# JetsonTK1_GPIO_V2.net
KiCad netlist of a schematic drawn in EAGLE
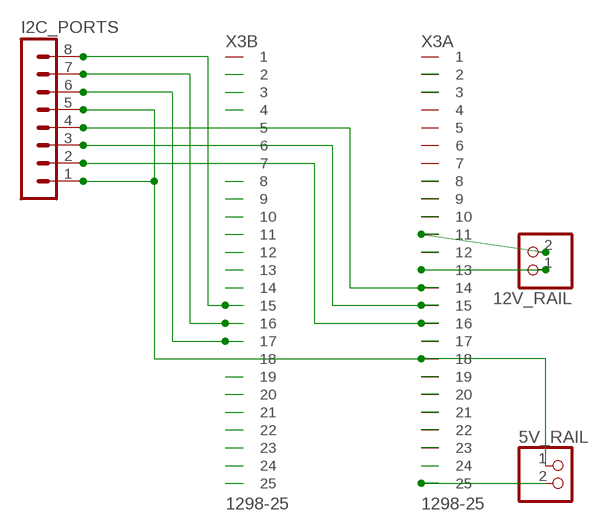
[diagram p0: schematic, sheet 1]

(export (version "E")
  (design (tool "Eeschema 10.0.6"))
  (components
    (comp (ref "5V_RAIL")
      (value "PINHD-1X2")
      (footprint "eagle-import:1X02")
      (libsource (lib "eagle-import") (part "PINHD-1X2"))
    )
    (comp (ref "12V_RAIL")
      (value "PINHD-1X2")
      (footprint "eagle-import:1X02")
      (libsource (lib "eagle-import") (part "PINHD-1X2"))
    )
    (comp (ref "I2C_PORTS")
      (value "MA08-1")
      (footprint "eagle-import:MA08-1")
      (libsource (lib "eagle-import") (part "MA08-1"))
    )
    (comp (ref "X3")
      (value "1298-25")
      (footprint "eagle-import:1298-25")
      (libsource (lib "eagle-import") (part "1298-25"))
    )
  )
  (nets
    (net (code "1") (name "Net-(X3A-11)") (class "Default")
      (node (ref "12V_RAIL") (pin "2") (pinfunction "2_2") (pintype "passive"))
      (node (ref "X3") (pin "A11") (pinfunction "11_A11") (pintype "passive"))
    )
    (net (code "2") (name "Net-(X3A-13)") (class "Default")
      (node (ref "12V_RAIL") (pin "1") (pinfunction "1_1") (pintype "passive"))
      (node (ref "X3") (pin "A13") (pinfunction "13_A13") (pintype "passive"))
    )
    (net (code "3") (name "Net-(X3A-14)") (class "Default")
      (node (ref "I2C_PORTS") (pin "4") (pinfunction "4_4") (pintype "passive"))
      (node (ref "X3") (pin "A14") (pinfunction "14_A14") (pintype "passive"))
    )
    (net (code "4") (name "Net-(X3A-15)") (class "Default")
      (node (ref "I2C_PORTS") (pin "3") (pinfunction "3_3") (pintype "passive"))
      (node (ref "X3") (pin "A15") (pinfunction "15_A15") (pintype "passive"))
    )
    (net (code "5") (name "Net-(X3A-16)") (class "Default")
      (node (ref "I2C_PORTS") (pin "2") (pinfunction "2_2") (pintype "passive"))
      (node (ref "X3") (pin "A16") (pinfunction "16_A16") (pintype "passive"))
    )
    (net (code "6") (name "Net-(X3A-18)") (class "Default")
      (node (ref "5V_RAIL") (pin "1") (pinfunction "1_1") (pintype "passive"))
      (node (ref "I2C_PORTS") (pin "1") (pinfunction "1_1") (pintype "passive"))
      (node (ref "I2C_PORTS") (pin "5") (pinfunction "5_5") (pintype "passive"))
      (node (ref "X3") (pin "A18") (pinfunction "18_A18") (pintype "passive"))
    )
    (net (code "7") (name "Net-(X3A-25)") (class "Default")
      (node (ref "5V_RAIL") (pin "2") (pinfunction "2_2") (pintype "passive"))
      (node (ref "X3") (pin "A25") (pinfunction "25_A25") (pintype "passive"))
    )
    (net (code "8") (name "Net-(X3B-15)") (class "Default")
      (node (ref "I2C_PORTS") (pin "8") (pinfunction "8_8") (pintype "passive"))
      (node (ref "X3") (pin "B15") (pinfunction "15_B15") (pintype "passive"))
    )
    (net (code "9") (name "Net-(X3B-16)") (class "Default")
      (node (ref "I2C_PORTS") (pin "7") (pinfunction "7_7") (pintype "passive"))
      (node (ref "X3") (pin "B16") (pinfunction "16_B16") (pintype "passive"))
    )
    (net (code "10") (name "Net-(X3B-17)") (class "Default")
      (node (ref "I2C_PORTS") (pin "6") (pinfunction "6_6") (pintype "passive"))
      (node (ref "X3") (pin "B17") (pinfunction "17_B17") (pintype "passive"))
    )
    (net (code "11") (name "unconnected-(X3A-1-PadA1)") (class "Default")
      (node (ref "X3") (pin "A1") (pinfunction "1_A1") (pintype "passive"))
    )
    (net (code "12") (name "unconnected-(X3A-2-PadA2)") (class "Default")
      (node (ref "X3") (pin "A2") (pinfunction "2_A2") (pintype "passive"))
    )
    (net (code "13") (name "unconnected-(X3A-3-PadA3)") (class "Default")
      (node (ref "X3") (pin "A3") (pinfunction "3_A3") (pintype "passive"))
    )
    (net (code "14") (name "unconnected-(X3A-4-PadA4)") (class "Default")
      (node (ref "X3") (pin "A4") (pinfunction "4_A4") (pintype "passive"))
    )
    (net (code "15") (name "unconnected-(X3A-5-PadA5)") (class "Default")
      (node (ref "X3") (pin "A5") (pinfunction "5_A5") (pintype "passive"))
    )
    (net (code "16") (name "unconnected-(X3A-6-PadA6)") (class "Default")
      (node (ref "X3") (pin "A6") (pinfunction "6_A6") (pintype "passive"))
    )
    (net (code "17") (name "unconnected-(X3A-7-PadA7)") (class "Default")
      (node (ref "X3") (pin "A7") (pinfunction "7_A7") (pintype "passive"))
    )
    (net (code "18") (name "unconnected-(X3A-8-PadA8)") (class "Default")
      (node (ref "X3") (pin "A8") (pinfunction "8_A8") (pintype "passive"))
    )
    (net (code "19") (name "unconnected-(X3A-9-PadA9)") (class "Default")
      (node (ref "X3") (pin "A9") (pinfunction "9_A9") (pintype "passive"))
    )
    (net (code "20") (name "unconnected-(X3A-10-PadA10)") (class "Default")
      (node (ref "X3") (pin "A10") (pinfunction "10_A10") (pintype "passive"))
    )
    (net (code "21") (name "unconnected-(X3A-12-PadA12)") (class "Default")
      (node (ref "X3") (pin "A12") (pinfunction "12_A12") (pintype "passive"))
    )
    (net (code "22") (name "unconnected-(X3A-17-PadA17)") (class "Default")
      (node (ref "X3") (pin "A17") (pinfunction "17_A17") (pintype "passive"))
    )
    (net (code "23") (name "unconnected-(X3A-19-PadA19)") (class "Default")
      (node (ref "X3") (pin "A19") (pinfunction "19_A19") (pintype "passive"))
    )
    (net (code "24") (name "unconnected-(X3A-20-PadA20)") (class "Default")
      (node (ref "X3") (pin "A20") (pinfunction "20_A20") (pintype "passive"))
    )
    (net (code "25") (name "unconnected-(X3A-21-PadA21)") (class "Default")
      (node (ref "X3") (pin "A21") (pinfunction "21_A21") (pintype "passive"))
    )
    (net (code "26") (name "unconnected-(X3A-22-PadA22)") (class "Default")
      (node (ref "X3") (pin "A22") (pinfunction "22_A22") (pintype "passive"))
    )
    (net (code "27") (name "unconnected-(X3A-23-PadA23)") (class "Default")
      (node (ref "X3") (pin "A23") (pinfunction "23_A23") (pintype "passive"))
    )
    (net (code "28") (name "unconnected-(X3A-24-PadA24)") (class "Default")
      (node (ref "X3") (pin "A24") (pinfunction "24_A24") (pintype "passive"))
    )
    (net (code "29") (name "unconnected-(X3B-1-PadB1)") (class "Default")
      (node (ref "X3") (pin "B1") (pinfunction "1_B1") (pintype "passive"))
    )
    (net (code "30") (name "unconnected-(X3B-2-PadB2)") (class "Default")
      (node (ref "X3") (pin "B2") (pinfunction "2_B2") (pintype "passive"))
    )
    (net (code "31") (name "unconnected-(X3B-3-PadB3)") (class "Default")
      (node (ref "X3") (pin "B3") (pinfunction "3_B3") (pintype "passive"))
    )
    (net (code "32") (name "unconnected-(X3B-4-PadB4)") (class "Default")
      (node (ref "X3") (pin "B4") (pinfunction "4_B4") (pintype "passive"))
    )
    (net (code "33") (name "unconnected-(X3B-5-PadB5)") (class "Default")
      (node (ref "X3") (pin "B5") (pinfunction "5_B5") (pintype "passive"))
    )
    (net (code "34") (name "unconnected-(X3B-6-PadB6)") (class "Default")
      (node (ref "X3") (pin "B6") (pinfunction "6_B6") (pintype "passive"))
    )
    (net (code "35") (name "unconnected-(X3B-7-PadB7)") (class "Default")
      (node (ref "X3") (pin "B7") (pinfunction "7_B7") (pintype "passive"))
    )
    (net (code "36") (name "unconnected-(X3B-8-PadB8)") (class "Default")
      (node (ref "X3") (pin "B8") (pinfunction "8_B8") (pintype "passive"))
    )
    (net (code "37") (name "unconnected-(X3B-9-PadB9)") (class "Default")
      (node (ref "X3") (pin "B9") (pinfunction "9_B9") (pintype "passive"))
    )
    (net (code "38") (name "unconnected-(X3B-10-PadB10)") (class "Default")
      (node (ref "X3") (pin "B10") (pinfunction "10_B10") (pintype "passive"))
    )
    (net (code "39") (name "unconnected-(X3B-11-PadB11)") (class "Default")
      (node (ref "X3") (pin "B11") (pinfunction "11_B11") (pintype "passive"))
    )
    (net (code "40") (name "unconnected-(X3B-12-PadB12)") (class "Default")
      (node (ref "X3") (pin "B12") (pinfunction "12_B12") (pintype "passive"))
    )
    (net (code "41") (name "unconnected-(X3B-13-PadB13)") (class "Default")
      (node (ref "X3") (pin "B13") (pinfunction "13_B13") (pintype "passive"))
    )
    (net (code "42") (name "unconnected-(X3B-14-PadB14)") (class "Default")
      (node (ref "X3") (pin "B14") (pinfunction "14_B14") (pintype "passive"))
    )
    (net (code "43") (name "unconnected-(X3B-18-PadB18)") (class "Default")
      (node (ref "X3") (pin "B18") (pinfunction "18_B18") (pintype "passive"))
    )
    (net (code "44") (name "unconnected-(X3B-19-PadB19)") (class "Default")
      (node (ref "X3") (pin "B19") (pinfunction "19_B19") (pintype "passive"))
    )
    (net (code "45") (name "unconnected-(X3B-20-PadB20)") (class "Default")
      (node (ref "X3") (pin "B20") (pinfunction "20_B20") (pintype "passive"))
    )
    (net (code "46") (name "unconnected-(X3B-21-PadB21)") (class "Default")
      (node (ref "X3") (pin "B21") (pinfunction "21_B21") (pintype "passive"))
    )
    (net (code "47") (name "unconnected-(X3B-22-PadB22)") (class "Default")
      (node (ref "X3") (pin "B22") (pinfunction "22_B22") (pintype "passive"))
    )
    (net (code "48") (name "unconnected-(X3B-23-PadB23)") (class "Default")
      (node (ref "X3") (pin "B23") (pinfunction "23_B23") (pintype "passive"))
    )
    (net (code "49") (name "unconnected-(X3B-24-PadB24)") (class "Default")
      (node (ref "X3") (pin "B24") (pinfunction "24_B24") (pintype "passive"))
    )
    (net (code "50") (name "unconnected-(X3B-25-PadB25)") (class "Default")
      (node (ref "X3") (pin "B25") (pinfunction "25_B25") (pintype "passive"))
    )
  )
)
